# CAN_Shield_HS.net
KiCad netlist of a schematic drawn in EAGLE
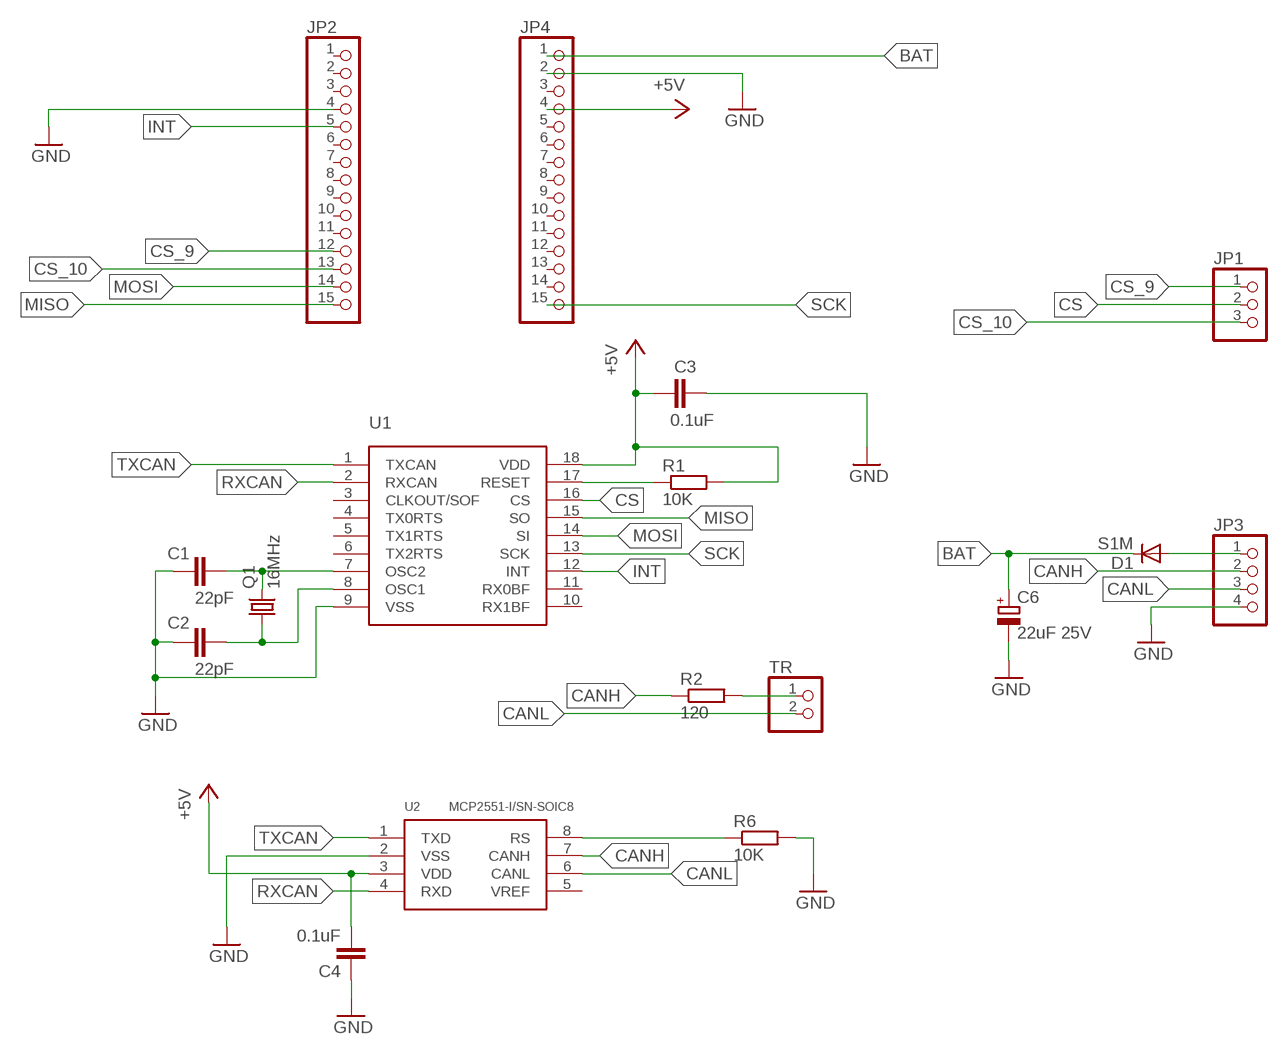
[diagram p0: schematic, sheet 1]

(export (version "E")
  (design (tool "Eeschema 10.0.6"))
  (components
    (comp (ref "C1")
      (value "22pF")
      (footprint "eagle-import:C0805")
      (libsource (lib "eagle-import") (part "C-EUC0805"))
    )
    (comp (ref "C2")
      (value "22pF")
      (footprint "eagle-import:C0805")
      (libsource (lib "eagle-import") (part "C-EUC0805"))
    )
    (comp (ref "C3")
      (value "0.1uF")
      (footprint "eagle-import:C0805")
      (libsource (lib "eagle-import") (part "C-EUC0805"))
    )
    (comp (ref "C4")
      (value "0.1uF")
      (footprint "eagle-import:C0805")
      (libsource (lib "eagle-import") (part "C-EUC0805"))
    )
    (comp (ref "C6")
      (value "22uF 25V")
      (footprint "eagle-import:SMC_C")
      (libsource (lib "eagle-import") (part "CPOL-EUSMCC"))
    )
    (comp (ref "D1")
      (value "S1M")
      (footprint "eagle-import:SMA")
      (libsource (lib "eagle-import") (part "S1M"))
    )
    (comp (ref "JP1")
      (value "PINHD-1X3")
      (footprint "eagle-import:1X03")
      (libsource (lib "eagle-import") (part "PINHD-1X3"))
    )
    (comp (ref "JP2")
      (value "PINHD-1X15")
      (footprint "eagle-import:1X15")
      (libsource (lib "eagle-import") (part "PINHD-1X15"))
    )
    (comp (ref "JP3")
      (value "PINHD-1X4-1")
      (footprint "eagle-import:1X04")
      (libsource (lib "eagle-import") (part "PINHD-1X4-1"))
    )
    (comp (ref "JP4")
      (value "PINHD-1X15")
      (footprint "eagle-import:1X15")
      (libsource (lib "eagle-import") (part "PINHD-1X15"))
    )
    (comp (ref "Q1")
      (value "16MHz")
      (footprint "eagle-import:HC49_S")
      (libsource (lib "eagle-import") (part "CRYSTALHC49S"))
    )
    (comp (ref "R1")
      (value "10K")
      (footprint "eagle-import:R0805")
      (libsource (lib "eagle-import") (part "R-EU_R0805"))
    )
    (comp (ref "R2")
      (value "120")
      (footprint "eagle-import:R0805")
      (libsource (lib "eagle-import") (part "R-EU_R0805"))
    )
    (comp (ref "R6")
      (value "10K")
      (footprint "eagle-import:R0805")
      (libsource (lib "eagle-import") (part "R-EU_R0805"))
    )
    (comp (ref "TR")
      (value "PINHD-1X2")
      (footprint "eagle-import:1X02")
      (libsource (lib "eagle-import") (part "PINHD-1X2"))
    )
    (comp (ref "U1")
      (value "MCP2515")
      (footprint "eagle-import:SO18-1")
      (libsource (lib "eagle-import") (part "MCP2515"))
    )
    (comp (ref "U2")
      (value "MCP2551-I/SN-SOIC8")
      (footprint "eagle-import:SOIC8-1.27-5X4MM")
      (fields (field (name "MPN") "MCP2551-I/SN"))
      (libsource (lib "eagle-import") (part "INTERFACE-MCP2551-I/SN(SOIC8)"))
    )
  )
  (nets
    (net (code "1") (name "+5V") (class "Default")
      (node (ref "C3") (pin "1") (pinfunction "1_1") (pintype "passive"))
      (node (ref "C4") (pin "2") (pinfunction "2_2") (pintype "passive"))
      (node (ref "JP4") (pin "4") (pinfunction "4_4") (pintype "passive"))
      (node (ref "R1") (pin "2") (pinfunction "2_2") (pintype "passive"))
      (node (ref "U1") (pin "18") (pinfunction "VDD_18") (pintype "power_in"))
      (node (ref "U2") (pin "3") (pinfunction "VDD_3") (pintype "bidirectional"))
    )
    (net (code "2") (name "BAT") (class "Default")
      (node (ref "C6") (pin "+") (pinfunction "+_+") (pintype "passive"))
      (node (ref "D1") (pin "C") (pinfunction "C_C") (pintype "passive"))
      (node (ref "JP4") (pin "1") (pinfunction "1_1") (pintype "passive"))
    )
    (net (code "3") (name "CANH") (class "Default")
      (node (ref "JP3") (pin "2") (pinfunction "2_2") (pintype "passive"))
      (node (ref "R2") (pin "1") (pinfunction "1_1") (pintype "passive"))
      (node (ref "U2") (pin "7") (pinfunction "CANH_7") (pintype "bidirectional"))
    )
    (net (code "4") (name "CANL") (class "Default")
      (node (ref "JP3") (pin "3") (pinfunction "3_3") (pintype "passive"))
      (node (ref "TR") (pin "2") (pinfunction "2_2") (pintype "passive"))
      (node (ref "U2") (pin "6") (pinfunction "CANL_6") (pintype "bidirectional"))
    )
    (net (code "5") (name "CS") (class "Default")
      (node (ref "JP1") (pin "2") (pinfunction "2_2") (pintype "passive"))
      (node (ref "U1") (pin "16") (pinfunction "CS_16") (pintype "bidirectional"))
    )
    (net (code "6") (name "CS_9") (class "Default")
      (node (ref "JP1") (pin "1") (pinfunction "1_1") (pintype "passive"))
      (node (ref "JP2") (pin "12") (pinfunction "12_12") (pintype "passive"))
    )
    (net (code "7") (name "CS_10") (class "Default")
      (node (ref "JP1") (pin "3") (pinfunction "3_3") (pintype "passive"))
      (node (ref "JP2") (pin "13") (pinfunction "13_13") (pintype "passive"))
    )
    (net (code "8") (name "GND") (class "Default")
      (node (ref "C1") (pin "1") (pinfunction "1_1") (pintype "passive"))
      (node (ref "C2") (pin "1") (pinfunction "1_1") (pintype "passive"))
      (node (ref "C3") (pin "2") (pinfunction "2_2") (pintype "passive"))
      (node (ref "C4") (pin "1") (pinfunction "1_1") (pintype "passive"))
      (node (ref "C6") (pin "-") (pinfunction "-_-") (pintype "passive"))
      (node (ref "JP2") (pin "4") (pinfunction "4_4") (pintype "passive"))
      (node (ref "JP3") (pin "4") (pinfunction "4_4") (pintype "passive"))
      (node (ref "JP4") (pin "2") (pinfunction "2_2") (pintype "passive"))
      (node (ref "R6") (pin "2") (pinfunction "2_2") (pintype "passive"))
      (node (ref "U1") (pin "9") (pinfunction "VSS_9") (pintype "power_in"))
      (node (ref "U2") (pin "2") (pinfunction "VSS_2") (pintype "bidirectional"))
    )
    (net (code "9") (name "INT") (class "Default")
      (node (ref "JP2") (pin "5") (pinfunction "5_5") (pintype "passive"))
      (node (ref "U1") (pin "12") (pinfunction "INT_12") (pintype "bidirectional"))
    )
    (net (code "10") (name "MISO") (class "Default")
      (node (ref "JP2") (pin "15") (pinfunction "15_15") (pintype "passive"))
      (node (ref "U1") (pin "15") (pinfunction "SO_15") (pintype "bidirectional"))
    )
    (net (code "11") (name "MOSI") (class "Default")
      (node (ref "JP2") (pin "14") (pinfunction "14_14") (pintype "passive"))
      (node (ref "U1") (pin "14") (pinfunction "SI_14") (pintype "bidirectional"))
    )
    (net (code "12") (name "Net-(D1-PadA)") (class "Default")
      (node (ref "D1") (pin "A") (pinfunction "A_A") (pintype "passive"))
      (node (ref "JP3") (pin "1") (pinfunction "1_1") (pintype "passive"))
    )
    (net (code "13") (name "Net-(R2-Pad2)") (class "Default")
      (node (ref "R2") (pin "2") (pinfunction "2_2") (pintype "passive"))
      (node (ref "TR") (pin "1") (pinfunction "1_1") (pintype "passive"))
    )
    (net (code "14") (name "Net-(U1-OSC1)") (class "Default")
      (node (ref "C2") (pin "2") (pinfunction "2_2") (pintype "passive"))
      (node (ref "Q1") (pin "1") (pinfunction "1_1") (pintype "passive"))
      (node (ref "U1") (pin "8") (pinfunction "OSC1_8") (pintype "bidirectional"))
    )
    (net (code "15") (name "Net-(U1-OSC2)") (class "Default")
      (node (ref "C1") (pin "2") (pinfunction "2_2") (pintype "passive"))
      (node (ref "Q1") (pin "2") (pinfunction "2_2") (pintype "passive"))
      (node (ref "U1") (pin "7") (pinfunction "OSC2_7") (pintype "bidirectional"))
    )
    (net (code "16") (name "Net-(U1-RESET)") (class "Default")
      (node (ref "R1") (pin "1") (pinfunction "1_1") (pintype "passive"))
      (node (ref "U1") (pin "17") (pinfunction "RESET_17") (pintype "bidirectional"))
    )
    (net (code "17") (name "Net-(U2-RS)") (class "Default")
      (node (ref "R6") (pin "1") (pinfunction "1_1") (pintype "passive"))
      (node (ref "U2") (pin "8") (pinfunction "RS_8") (pintype "bidirectional"))
    )
    (net (code "18") (name "RXCAN") (class "Default")
      (node (ref "U1") (pin "2") (pinfunction "RXCAN_2") (pintype "bidirectional"))
      (node (ref "U2") (pin "4") (pinfunction "RXD_4") (pintype "bidirectional"))
    )
    (net (code "19") (name "SCK") (class "Default")
      (node (ref "JP4") (pin "15") (pinfunction "15_15") (pintype "passive"))
      (node (ref "U1") (pin "13") (pinfunction "SCK_13") (pintype "bidirectional"))
    )
    (net (code "20") (name "TXCAN") (class "Default")
      (node (ref "U1") (pin "1") (pinfunction "TXCAN_1") (pintype "bidirectional"))
      (node (ref "U2") (pin "1") (pinfunction "TXD_1") (pintype "bidirectional"))
    )
    (net (code "21") (name "unconnected-(JP2-Pad1)") (class "Default")
      (node (ref "JP2") (pin "1") (pinfunction "1_1") (pintype "passive"))
    )
    (net (code "22") (name "unconnected-(JP2-Pad2)") (class "Default")
      (node (ref "JP2") (pin "2") (pinfunction "2_2") (pintype "passive"))
    )
    (net (code "23") (name "unconnected-(JP2-Pad3)") (class "Default")
      (node (ref "JP2") (pin "3") (pinfunction "3_3") (pintype "passive"))
    )
    (net (code "24") (name "unconnected-(JP2-Pad6)") (class "Default")
      (node (ref "JP2") (pin "6") (pinfunction "6_6") (pintype "passive"))
    )
    (net (code "25") (name "unconnected-(JP2-Pad7)") (class "Default")
      (node (ref "JP2") (pin "7") (pinfunction "7_7") (pintype "passive"))
    )
    (net (code "26") (name "unconnected-(JP2-Pad8)") (class "Default")
      (node (ref "JP2") (pin "8") (pinfunction "8_8") (pintype "passive"))
    )
    (net (code "27") (name "unconnected-(JP2-Pad9)") (class "Default")
      (node (ref "JP2") (pin "9") (pinfunction "9_9") (pintype "passive"))
    )
    (net (code "28") (name "unconnected-(JP2-Pad10)") (class "Default")
      (node (ref "JP2") (pin "10") (pinfunction "10_10") (pintype "passive"))
    )
    (net (code "29") (name "unconnected-(JP2-Pad11)") (class "Default")
      (node (ref "JP2") (pin "11") (pinfunction "11_11") (pintype "passive"))
    )
    (net (code "30") (name "unconnected-(JP4-Pad3)") (class "Default")
      (node (ref "JP4") (pin "3") (pinfunction "3_3") (pintype "passive"))
    )
    (net (code "31") (name "unconnected-(JP4-Pad5)") (class "Default")
      (node (ref "JP4") (pin "5") (pinfunction "5_5") (pintype "passive"))
    )
    (net (code "32") (name "unconnected-(JP4-Pad6)") (class "Default")
      (node (ref "JP4") (pin "6") (pinfunction "6_6") (pintype "passive"))
    )
    (net (code "33") (name "unconnected-(JP4-Pad7)") (class "Default")
      (node (ref "JP4") (pin "7") (pinfunction "7_7") (pintype "passive"))
    )
    (net (code "34") (name "unconnected-(JP4-Pad8)") (class "Default")
      (node (ref "JP4") (pin "8") (pinfunction "8_8") (pintype "passive"))
    )
    (net (code "35") (name "unconnected-(JP4-Pad9)") (class "Default")
      (node (ref "JP4") (pin "9") (pinfunction "9_9") (pintype "passive"))
    )
    (net (code "36") (name "unconnected-(JP4-Pad10)") (class "Default")
      (node (ref "JP4") (pin "10") (pinfunction "10_10") (pintype "passive"))
    )
    (net (code "37") (name "unconnected-(JP4-Pad11)") (class "Default")
      (node (ref "JP4") (pin "11") (pinfunction "11_11") (pintype "passive"))
    )
    (net (code "38") (name "unconnected-(JP4-Pad12)") (class "Default")
      (node (ref "JP4") (pin "12") (pinfunction "12_12") (pintype "passive"))
    )
    (net (code "39") (name "unconnected-(JP4-Pad13)") (class "Default")
      (node (ref "JP4") (pin "13") (pinfunction "13_13") (pintype "passive"))
    )
    (net (code "40") (name "unconnected-(JP4-Pad14)") (class "Default")
      (node (ref "JP4") (pin "14") (pinfunction "14_14") (pintype "passive"))
    )
    (net (code "41") (name "unconnected-(U1-CLKOUT{slash}SOF-Pad3)") (class "Default")
      (node (ref "U1") (pin "3") (pinfunction "CLKOUT/SOF_3") (pintype "bidirectional"))
    )
    (net (code "42") (name "unconnected-(U1-RX0BF-Pad11)") (class "Default")
      (node (ref "U1") (pin "11") (pinfunction "RX0BF_11") (pintype "bidirectional"))
    )
    (net (code "43") (name "unconnected-(U1-RX1BF-Pad10)") (class "Default")
      (node (ref "U1") (pin "10") (pinfunction "RX1BF_10") (pintype "bidirectional"))
    )
    (net (code "44") (name "unconnected-(U1-TX0RTS-Pad4)") (class "Default")
      (node (ref "U1") (pin "4") (pinfunction "TX0RTS_4") (pintype "bidirectional"))
    )
    (net (code "45") (name "unconnected-(U1-TX1RTS-Pad5)") (class "Default")
      (node (ref "U1") (pin "5") (pinfunction "TX1RTS_5") (pintype "bidirectional"))
    )
    (net (code "46") (name "unconnected-(U1-TX2RTS-Pad6)") (class "Default")
      (node (ref "U1") (pin "6") (pinfunction "TX2RTS_6") (pintype "bidirectional"))
    )
    (net (code "47") (name "unconnected-(U2-VREF-Pad5)") (class "Default")
      (node (ref "U2") (pin "5") (pinfunction "VREF_5") (pintype "bidirectional"))
    )
  )
)
